# USB.net
KiCad netlist of a schematic drawn in Altium Designer
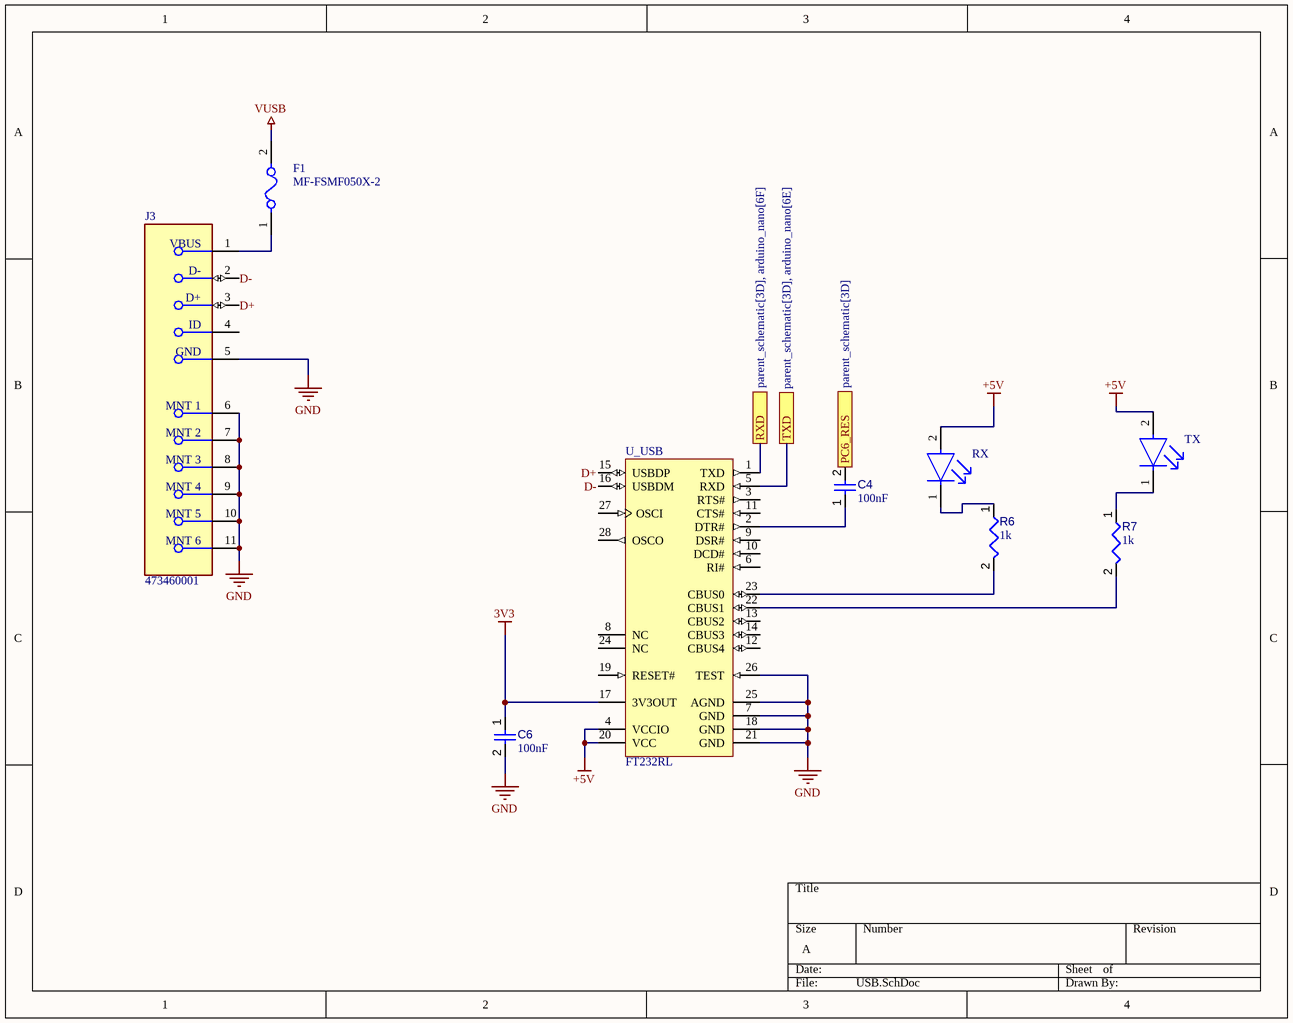
[diagram p0: USB.SchDoc]

(export (version "E")
  (design (tool "Eeschema 10.0.6"))
  (components
    (comp (ref "C4")
      (value "100nF")
      (footprint "CAPC0402(1005)60_L")
      (description "Chip Capacitor, 100nF +/-20%, 25V, 0402, Thickness 0.6 mm")
      (fields (field (name "TOLERANCE") "10%") (field (name "Comment") "Capacitor 100nF +/-20% 25V 0402"))
      (libsource (lib "Widha Rizqika Prasetya") (part "CAP-NP-2"))
    )
    (comp (ref "C6")
      (value "100nF")
      (footprint "CAPC0402(1005)60_L")
      (description "Chip Capacitor, 100nF +/-20%, 25V, 0402, Thickness 0.6 mm")
      (fields (field (name "TOLERANCE") "10%") (field (name "Comment") "Capacitor 100nF +/-20% 25V 0402"))
      (libsource (lib "Widha Rizqika Prasetya") (part "CAP-NP-2"))
    )
    (comp (ref "F1")
      (value "MF-FSMF050X-2")
      (footprint "FP-MF-FSMF-MFG")
      (description "PTC RESET FUSE 6V 500MA 0603")
      (fields
        (field (name "MANUFACTURER") "Bourns Inc.")
        (field (name "OCTOPART") "https://octopart.com/mf-fsmf050x-2-bourns-10470804")
      )
      (libsource (lib "Altium Content Vault") (part "5bcf9b9f640e542cf0359d10258e979"))
    )
    (comp (ref "J3")
      (value "473460001")
      (footprint "FP-473460001-MFG")
      (description "CONN RCPT USB2.0 MICRO B SMD R/A")
      (fields
        (field (name "OCTOPART") "https://octopart.com/47346-0001-molex-7164928")
        (field (name "MANUFACTURER") "Molex")
      )
      (libsource (lib "Altium Content Vault") (part "53ae1f1d9b557310b43ca686e5bb76a"))
    )
    (comp (ref "R6")
      (value "1k")
      (footprint "RESC2012X70N")
      (description "Res Thick Film 0805 1K Ohm 5% 0.5W(1/2W) ±200ppm/C Pad SMD Automotive T/R")
      (fields (field (name "TOLERANCE") "5%") (field (name "Comment") "ERJP06J102V_with_model"))
      (libsource (lib "Widha Rizqika Prasetya") (part "RES-2"))
    )
    (comp (ref "R7")
      (value "1k")
      (footprint "RESC2012X70N")
      (description "Res Thick Film 0805 1K Ohm 5% 0.5W(1/2W) ±200ppm/C Pad SMD Automotive T/R")
      (fields (field (name "TOLERANCE") "5%") (field (name "Comment") "ERJP06J102V_with_model"))
      (libsource (lib "Widha Rizqika Prasetya") (part "RES-2"))
    )
    (comp (ref "RX")
      (value "~")
      (footprint "FP-APTD1608SYC-J3-MFG")
      (description "LED YELLOW CLEAR CHIP SMD")
      (libsource (lib "Altium Content Vault") (part "8706943c75ba83719d021d2fdc84c58"))
    )
    (comp (ref "TX")
      (value "~")
      (footprint "FP-APTD1608SYC-J3-MFG")
      (description "LED YELLOW CLEAR CHIP SMD")
      (libsource (lib "Altium Content Vault") (part "8706943c75ba83719d021d2fdc84c58"))
    )
    (comp (ref "U_USB")
      (value "FT232RL")
      (footprint "FTDI-SSOP-28_M")
      (description "IC USB FS SERIAL UART 28-SSOP")
      (fields (field (name "MANUFACTURER") "FTDI"))
      (libsource (lib "Altium Content Vault") (part "FTDI-FT232-SSOP-28"))
    )
  )
  (nets
    (net (code "1") (name "+5V") (class "Default")
      (node (ref "RX") (pin "2") (pinfunction "A_2") (pintype "passive"))
      (node (ref "TX") (pin "2") (pinfunction "A_2") (pintype "passive"))
      (node (ref "U_USB") (pin "20") (pinfunction "VCC_20") (pintype "power_in"))
      (node (ref "U_USB") (pin "4") (pinfunction "VCCIO_4") (pintype "power_in"))
    )
    (net (code "2") (name "/D+") (class "Default")
      (node (ref "J3") (pin "3") (pinfunction "D+_3") (pintype "bidirectional"))
      (node (ref "U_USB") (pin "15") (pinfunction "USBDP_15") (pintype "bidirectional"))
    )
    (net (code "3") (name "/D-") (class "Default")
      (node (ref "J3") (pin "2") (pinfunction "D-_2") (pintype "bidirectional"))
      (node (ref "U_USB") (pin "16") (pinfunction "USBDM_16") (pintype "bidirectional"))
    )
    (net (code "4") (name "/PC6_RES") (class "Default")
      (node (ref "C4") (pin "2") (pinfunction "2_2") (pintype "passive"))
    )
    (net (code "5") (name "/RXD") (class "Default")
      (node (ref "U_USB") (pin "1") (pinfunction "TXD_1") (pintype "output"))
    )
    (net (code "6") (name "/TXD") (class "Default")
      (node (ref "U_USB") (pin "5") (pinfunction "RXD_5") (pintype "input"))
    )
    (net (code "7") (name "3V3") (class "Default")
      (node (ref "C6") (pin "1") (pinfunction "1_1") (pintype "passive"))
      (node (ref "U_USB") (pin "17") (pinfunction "3V3OUT_17") (pintype "power_in"))
    )
    (net (code "8") (name "GND") (class "Default")
      (node (ref "C6") (pin "2") (pinfunction "2_2") (pintype "passive"))
      (node (ref "J3") (pin "10") (pinfunction "MNT_5_10") (pintype "passive"))
      (node (ref "J3") (pin "11") (pinfunction "MNT_6_11") (pintype "passive"))
      (node (ref "J3") (pin "5") (pinfunction "GND_5") (pintype "power_in"))
      (node (ref "J3") (pin "6") (pinfunction "MNT_1_6") (pintype "passive"))
      (node (ref "J3") (pin "7") (pinfunction "MNT_2_7") (pintype "passive"))
      (node (ref "J3") (pin "8") (pinfunction "MNT_3_8") (pintype "passive"))
      (node (ref "J3") (pin "9") (pinfunction "MNT_4_9") (pintype "passive"))
      (node (ref "U_USB") (pin "18") (pinfunction "GND_18") (pintype "power_in"))
      (node (ref "U_USB") (pin "21") (pinfunction "GND_21") (pintype "power_in"))
      (node (ref "U_USB") (pin "25") (pinfunction "AGND_25") (pintype "power_in"))
      (node (ref "U_USB") (pin "26") (pinfunction "TEST_26") (pintype "input"))
      (node (ref "U_USB") (pin "7") (pinfunction "GND_7") (pintype "power_in"))
    )
    (net (code "9") (name "Net-(J3-VBUS)") (class "Default")
      (node (ref "F1") (pin "1") (pinfunction "1_1") (pintype "passive"))
      (node (ref "J3") (pin "1") (pinfunction "VBUS_1") (pintype "power_in"))
    )
    (net (code "10") (name "Net-(RX-C)") (class "Default")
      (node (ref "R6") (pin "1") (pinfunction "1_1") (pintype "passive"))
      (node (ref "RX") (pin "1") (pinfunction "C_1") (pintype "passive"))
    )
    (net (code "11") (name "Net-(TX-C)") (class "Default")
      (node (ref "R7") (pin "1") (pinfunction "1_1") (pintype "passive"))
      (node (ref "TX") (pin "1") (pinfunction "C_1") (pintype "passive"))
    )
    (net (code "12") (name "Net-(U_USB-CBUS0)") (class "Default")
      (node (ref "R6") (pin "2") (pinfunction "2_2") (pintype "passive"))
      (node (ref "U_USB") (pin "23") (pinfunction "CBUS0_23") (pintype "bidirectional"))
    )
    (net (code "13") (name "Net-(U_USB-CBUS1)") (class "Default")
      (node (ref "R7") (pin "2") (pinfunction "2_2") (pintype "passive"))
      (node (ref "U_USB") (pin "22") (pinfunction "CBUS1_22") (pintype "bidirectional"))
    )
    (net (code "14") (name "Net-(U_USB-DTR#)") (class "Default")
      (node (ref "C4") (pin "1") (pinfunction "1_1") (pintype "passive"))
      (node (ref "U_USB") (pin "2") (pinfunction "DTR#_2") (pintype "output"))
    )
    (net (code "15") (name "VUSB") (class "Default")
      (node (ref "F1") (pin "2") (pinfunction "2_2") (pintype "passive"))
    )
    (net (code "16") (name "unconnected-(J3-ID-Pad4)") (class "Default")
      (node (ref "J3") (pin "4") (pinfunction "ID_4") (pintype "passive"))
    )
    (net (code "17") (name "unconnected-(U_USB-CBUS2-Pad13)") (class "Default")
      (node (ref "U_USB") (pin "13") (pinfunction "CBUS2_13") (pintype "bidirectional"))
    )
    (net (code "18") (name "unconnected-(U_USB-CBUS3-Pad14)") (class "Default")
      (node (ref "U_USB") (pin "14") (pinfunction "CBUS3_14") (pintype "bidirectional"))
    )
    (net (code "19") (name "unconnected-(U_USB-CBUS4-Pad12)") (class "Default")
      (node (ref "U_USB") (pin "12") (pinfunction "CBUS4_12") (pintype "bidirectional"))
    )
    (net (code "20") (name "unconnected-(U_USB-CTS#-Pad11)") (class "Default")
      (node (ref "U_USB") (pin "11") (pinfunction "CTS#_11") (pintype "input"))
    )
    (net (code "21") (name "unconnected-(U_USB-DCD#-Pad10)") (class "Default")
      (node (ref "U_USB") (pin "10") (pinfunction "DCD#_10") (pintype "input"))
    )
    (net (code "22") (name "unconnected-(U_USB-DSR#-Pad9)") (class "Default")
      (node (ref "U_USB") (pin "9") (pinfunction "DSR#_9") (pintype "input"))
    )
    (net (code "23") (name "unconnected-(U_USB-NC-Pad8)") (class "Default")
      (node (ref "U_USB") (pin "8") (pinfunction "NC_8") (pintype "passive"))
    )
    (net (code "24") (name "unconnected-(U_USB-NC-Pad24)") (class "Default")
      (node (ref "U_USB") (pin "24") (pinfunction "NC_24") (pintype "passive"))
    )
    (net (code "25") (name "unconnected-(U_USB-OSCI-Pad27)") (class "Default")
      (node (ref "U_USB") (pin "27") (pinfunction "OSCI_27") (pintype "input"))
    )
    (net (code "26") (name "unconnected-(U_USB-OSCO-Pad28)") (class "Default")
      (node (ref "U_USB") (pin "28") (pinfunction "OSCO_28") (pintype "output"))
    )
    (net (code "27") (name "unconnected-(U_USB-RESET#-Pad19)") (class "Default")
      (node (ref "U_USB") (pin "19") (pinfunction "RESET#_19") (pintype "input"))
    )
    (net (code "28") (name "unconnected-(U_USB-RI#-Pad6)") (class "Default")
      (node (ref "U_USB") (pin "6") (pinfunction "RI#_6") (pintype "input"))
    )
    (net (code "29") (name "unconnected-(U_USB-RTS#-Pad3)") (class "Default")
      (node (ref "U_USB") (pin "3") (pinfunction "RTS#_3") (pintype "output"))
    )
  )
)
